# Microcontroller.net
KiCad netlist of a schematic drawn in Altium Designer
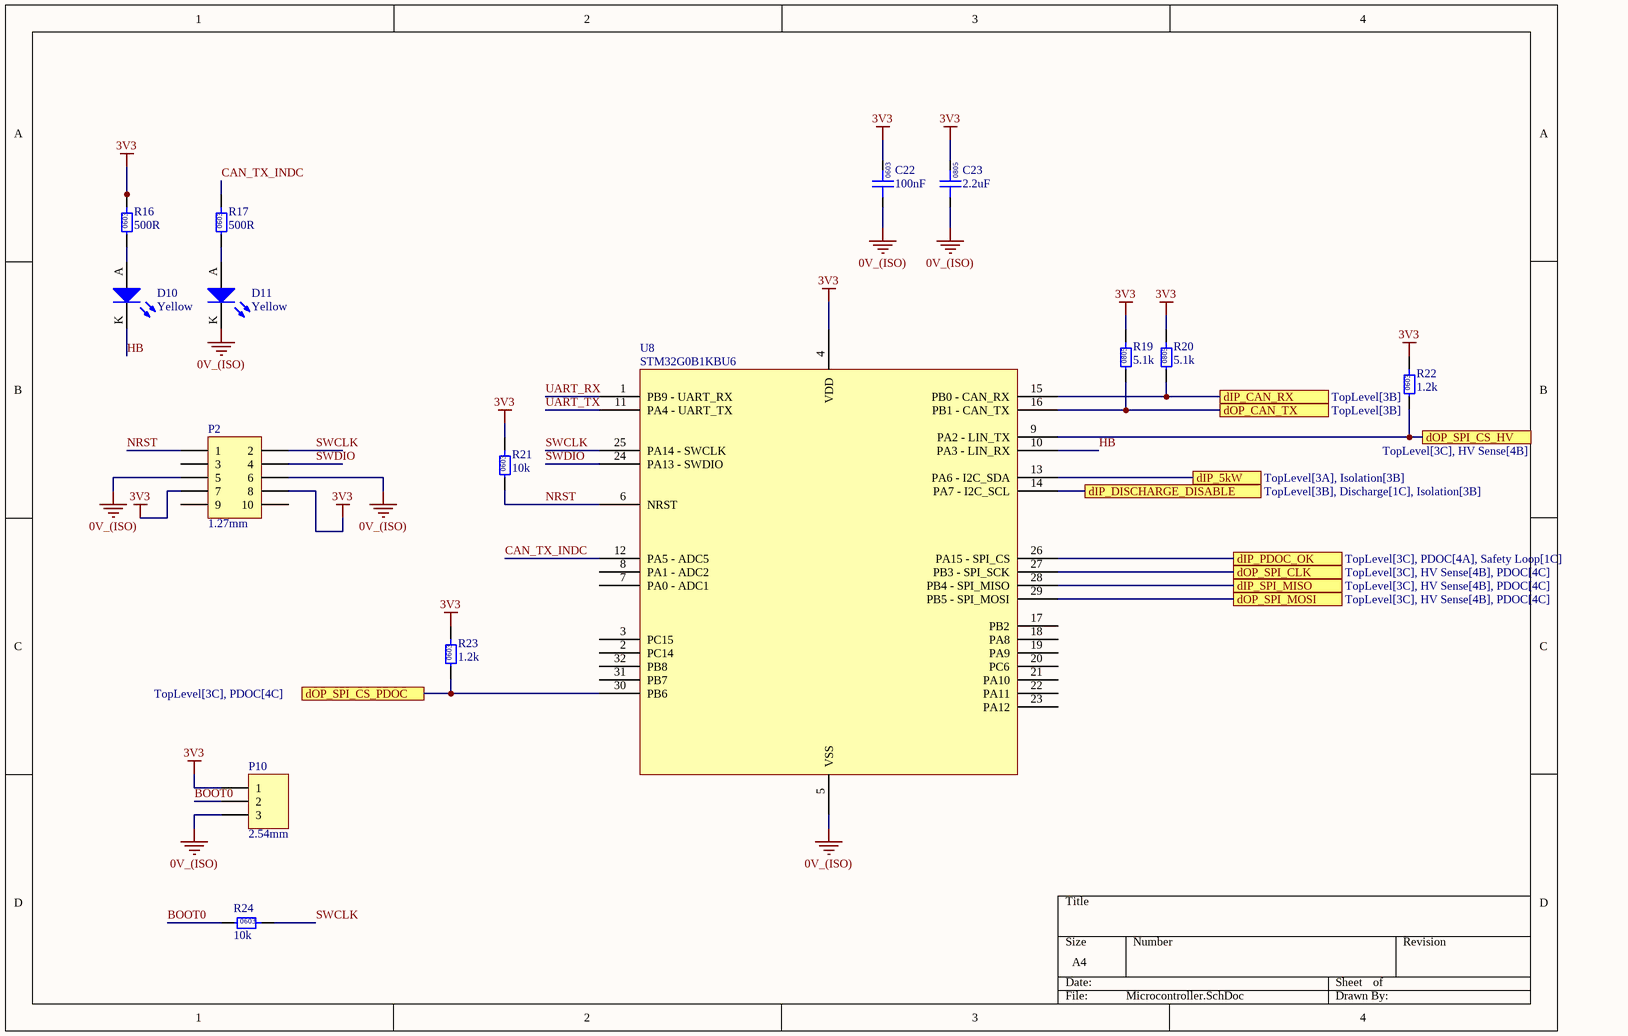
[diagram p0: Microcontroller.SchDoc]

(export (version "E")
  (design (tool "Eeschema 10.0.6"))
  (components
    (comp (ref "C22")
      (value "100nF")
      (footprint "0603 Capacitor")
      (fields (field (name "TOLERANCE") "10%") (field (name "PART NUMBER") "GCM188L81H104KA57D"))
      (libsource (lib "Team Swinburne") (part "100nF"))
    )
    (comp (ref "C23")
      (value "2.2uF")
      (footprint "GCM21BR71H105KA03L-Footprint-1")
      (fields (field (name "TOLERANCE") "10%") (field (name "PART NUMBER") "GRM21BR71E225KE11L"))
      (libsource (lib "Team Swinburne") (part "Component_1"))
    )
    (comp (ref "D10")
      (value "Yellow")
      (footprint "0805 LED")
      (description "Yellow LED Indication - Discrete 1.75V 0805 (2012 Metric)")
      (fields (field (name "PART NUMBER") "SML-211YTT86") (field (name "MANUFACTURER") "ROHM Semiconductor"))
      (libsource (lib "ts_standard_library") (part "LED"))
    )
    (comp (ref "D11")
      (value "Yellow")
      (footprint "0805 LED")
      (description "Yellow LED Indication - Discrete 1.75V 0805 (2012 Metric)")
      (fields (field (name "PART NUMBER") "SML-211YTT86") (field (name "MANUFACTURER") "ROHM Semiconductor"))
      (libsource (lib "ts_standard_library") (part "LED"))
    )
    (comp (ref "P2")
      (value "1.27mm")
      (footprint "3221-10-0300-00")
      (fields
        (field (name "PART NUMBER") "SMD 1.27mm Header 2x5 (3221-10-0300-00)")
        (field (name "CONTACT") "NA")
      )
      (libsource (lib "ts_standard_connectors") (part "Header 2x5"))
    )
    (comp (ref "P10")
      (value "2.54mm")
      (footprint "TH 2.54mm Header 1x3")
      (fields (field (name "PART NUMBER") "TH 2.54mm Header 1x3") (field (name "CONTACT") "NA"))
      (libsource (lib "ts_standard_connectors") (part "Header 1x3"))
    )
    (comp (ref "R16")
      (value "500R")
      (footprint "0603")
      (fields
        (field (name "PART NUMBER") "RT0603BRD07500RL")
        (field (name "MANUFACTURER") "YAGEO")
        (field (name "TOLERANCE") "0.01")
      )
      (libsource (lib "ts_standard_library") (part "Resistor 0603"))
    )
    (comp (ref "R17")
      (value "500R")
      (footprint "0603")
      (fields
        (field (name "PART NUMBER") "RT0603BRD07500RL")
        (field (name "MANUFACTURER") "YAGEO")
        (field (name "TOLERANCE") "0.01")
      )
      (libsource (lib "ts_standard_library") (part "Resistor 0603"))
    )
    (comp (ref "R19")
      (value "5.1k")
      (footprint "0805")
      (fields
        (field (name "PART NUMBER") "RC0805FR075K1L")
        (field (name "MANUFACTURER") "YAGEO")
        (field (name "TOLERANCE") "0.01")
      )
      (libsource (lib "ts_standard_library") (part "Resistor 0805"))
    )
    (comp (ref "R20")
      (value "5.1k")
      (footprint "0805")
      (fields
        (field (name "PART NUMBER") "RC0805FR075K1L")
        (field (name "MANUFACTURER") "YAGEO")
        (field (name "TOLERANCE") "0.01")
      )
      (libsource (lib "ts_standard_library") (part "Resistor 0805"))
    )
    (comp (ref "R21")
      (value "10k")
      (footprint "0603")
      (fields
        (field (name "PART NUMBER") "RC0603FR-0710KL")
        (field (name "MANUFACTURER") "YAGEO")
        (field (name "TOLERANCE") "0.01")
      )
      (libsource (lib "ts_standard_library") (part "Resistor 0603"))
    )
    (comp (ref "R22")
      (value "1.2k")
      (footprint "0603")
      (fields
        (field (name "PART NUMBER") "RC0603JR-071K2L")
        (field (name "MANUFACTURER") "YAGEO")
        (field (name "TOLERANCE") "0.01")
      )
      (libsource (lib "ts_standard_library") (part "Resistor 0603"))
    )
    (comp (ref "R23")
      (value "1.2k")
      (footprint "0603")
      (fields
        (field (name "PART NUMBER") "RC0603JR-071K2L")
        (field (name "MANUFACTURER") "YAGEO")
        (field (name "TOLERANCE") "0.01")
      )
      (libsource (lib "ts_standard_library") (part "Resistor 0603"))
    )
    (comp (ref "R24")
      (value "10k")
      (footprint "0603")
      (fields
        (field (name "PART NUMBER") "RC0603FR-0710KL")
        (field (name "MANUFACTURER") "YAGEO")
        (field (name "TOLERANCE") "0.01")
      )
      (libsource (lib "ts_standard_library") (part "Resistor 0603"))
    )
    (comp (ref "U8")
      (value "STM32G0B1KBU6")
      (footprint "ST-UFQFPN32")
      (description "RISC Microcontroller, 32-Bit, FLASH, Cortex-M0+ CPU, 64MHz, CMOS")
      (libsource (lib "Team Swinburne") (part "STM32G0B1KBU6"))
    )
  )
  (nets
    (net (code "1") (name "/BOOT0") (class "Default")
      (node (ref "P10") (pin "2") (pinfunction "2_2") (pintype "passive"))
      (node (ref "R24") (pin "1") (pinfunction "1_1") (pintype "passive"))
    )
    (net (code "2") (name "/CAN_TX_INDC") (class "Default")
      (node (ref "R17") (pin "2") (pinfunction "2_2") (pintype "passive"))
      (node (ref "U8") (pin "12") (pinfunction "PA5_-_ADC5_12") (pintype "passive"))
    )
    (net (code "3") (name "/HB") (class "Default")
      (node (ref "D10") (pin "K") (pinfunction "K_K") (pintype "passive"))
      (node (ref "U8") (pin "10") (pinfunction "PA3_-_LIN_RX_10") (pintype "passive"))
    )
    (net (code "4") (name "/NRST") (class "Default")
      (node (ref "P2") (pin "1") (pinfunction "1_1") (pintype "passive"))
      (node (ref "R21") (pin "1") (pinfunction "1_1") (pintype "passive"))
      (node (ref "U8") (pin "6") (pinfunction "NRST_6") (pintype "passive"))
    )
    (net (code "5") (name "/SWCLK") (class "Default")
      (node (ref "P2") (pin "2") (pinfunction "2_2") (pintype "passive"))
      (node (ref "R24") (pin "2") (pinfunction "2_2") (pintype "passive"))
      (node (ref "U8") (pin "25") (pinfunction "PA14_-_SWCLK_25") (pintype "passive"))
    )
    (net (code "6") (name "/SWDIO") (class "Default")
      (node (ref "P2") (pin "4") (pinfunction "4_4") (pintype "passive"))
      (node (ref "U8") (pin "24") (pinfunction "PA13_-_SWDIO_24") (pintype "passive"))
    )
    (net (code "7") (name "/UART_RX") (class "Default")
      (node (ref "U8") (pin "1") (pinfunction "PB9_-_UART_RX_1") (pintype "passive"))
    )
    (net (code "8") (name "/UART_TX") (class "Default")
      (node (ref "U8") (pin "11") (pinfunction "PA4_-_UART_TX_11") (pintype "passive"))
    )
    (net (code "9") (name "/dIP_5kW") (class "Default")
      (node (ref "U8") (pin "13") (pinfunction "PA6_-_I2C_SDA_13") (pintype "passive"))
    )
    (net (code "10") (name "/dIP_CAN_RX") (class "Default")
      (node (ref "R20") (pin "1") (pinfunction "1_1") (pintype "passive"))
      (node (ref "U8") (pin "15") (pinfunction "PB0_-_CAN_RX_15") (pintype "passive"))
    )
    (net (code "11") (name "/dIP_DISCHARGE_DISABLE") (class "Default")
      (node (ref "U8") (pin "14") (pinfunction "PA7_-_I2C_SCL_14") (pintype "passive"))
    )
    (net (code "12") (name "/dIP_PDOC_OK") (class "Default")
      (node (ref "U8") (pin "26") (pinfunction "PA15_-_SPI_CS_26") (pintype "passive"))
    )
    (net (code "13") (name "/dIP_SPI_MISO") (class "Default")
      (node (ref "U8") (pin "28") (pinfunction "PB4_-_SPI_MISO_28") (pintype "passive"))
    )
    (net (code "14") (name "/dOP_CAN_TX") (class "Default")
      (node (ref "R19") (pin "1") (pinfunction "1_1") (pintype "passive"))
      (node (ref "U8") (pin "16") (pinfunction "PB1_-_CAN_TX_16") (pintype "passive"))
    )
    (net (code "15") (name "/dOP_SPI_CLK") (class "Default")
      (node (ref "U8") (pin "27") (pinfunction "PB3_-_SPI_SCK_27") (pintype "passive"))
    )
    (net (code "16") (name "/dOP_SPI_CS_HV") (class "Default")
      (node (ref "R22") (pin "1") (pinfunction "1_1") (pintype "passive"))
      (node (ref "U8") (pin "9") (pinfunction "PA2_-_LIN_TX_9") (pintype "passive"))
    )
    (net (code "17") (name "/dOP_SPI_CS_PDOC") (class "Default")
      (node (ref "R23") (pin "1") (pinfunction "1_1") (pintype "passive"))
      (node (ref "U8") (pin "30") (pinfunction "PB6_30") (pintype "passive"))
    )
    (net (code "18") (name "/dOP_SPI_MOSI") (class "Default")
      (node (ref "U8") (pin "29") (pinfunction "PB5_-_SPI_MOSI_29") (pintype "passive"))
    )
    (net (code "19") (name "0V_(ISO)") (class "Default")
      (node (ref "C22") (pin "1") (pinfunction "1_1") (pintype "passive"))
      (node (ref "C23") (pin "1") (pinfunction "1_1") (pintype "passive"))
      (node (ref "D11") (pin "K") (pinfunction "K_K") (pintype "passive"))
      (node (ref "P10") (pin "3") (pinfunction "3_3") (pintype "passive"))
      (node (ref "P2") (pin "5") (pinfunction "5_5") (pintype "passive"))
      (node (ref "P2") (pin "6") (pinfunction "6_6") (pintype "passive"))
      (node (ref "U8") (pin "5") (pinfunction "VSS_5") (pintype "passive"))
    )
    (net (code "20") (name "3V3") (class "Default")
      (node (ref "C22") (pin "2") (pinfunction "2_2") (pintype "passive"))
      (node (ref "C23") (pin "2") (pinfunction "2_2") (pintype "passive"))
      (node (ref "P10") (pin "1") (pinfunction "1_1") (pintype "passive"))
      (node (ref "P2") (pin "7") (pinfunction "7_7") (pintype "passive"))
      (node (ref "P2") (pin "8") (pinfunction "8_8") (pintype "passive"))
      (node (ref "R16") (pin "2") (pinfunction "2_2") (pintype "passive"))
      (node (ref "R19") (pin "2") (pinfunction "2_2") (pintype "passive"))
      (node (ref "R20") (pin "2") (pinfunction "2_2") (pintype "passive"))
      (node (ref "R21") (pin "2") (pinfunction "2_2") (pintype "passive"))
      (node (ref "R22") (pin "2") (pinfunction "2_2") (pintype "passive"))
      (node (ref "R23") (pin "2") (pinfunction "2_2") (pintype "passive"))
      (node (ref "U8") (pin "4") (pinfunction "VDD_4") (pintype "passive"))
    )
    (net (code "21") (name "Net-(D10-PadA)") (class "Default")
      (node (ref "D10") (pin "A") (pinfunction "A_A") (pintype "passive"))
      (node (ref "R16") (pin "1") (pinfunction "1_1") (pintype "passive"))
    )
    (net (code "22") (name "Net-(D11-PadA)") (class "Default")
      (node (ref "D11") (pin "A") (pinfunction "A_A") (pintype "passive"))
      (node (ref "R17") (pin "1") (pinfunction "1_1") (pintype "passive"))
    )
    (net (code "23") (name "unconnected-(P2-Pad3)") (class "Default")
      (node (ref "P2") (pin "3") (pinfunction "3_3") (pintype "passive"))
    )
    (net (code "24") (name "unconnected-(P2-Pad9)") (class "Default")
      (node (ref "P2") (pin "9") (pinfunction "9_9") (pintype "passive"))
    )
    (net (code "25") (name "unconnected-(P2-Pad10)") (class "Default")
      (node (ref "P2") (pin "10") (pinfunction "10_10") (pintype "passive"))
    )
    (net (code "26") (name "unconnected-(U8-PA0_-_ADC1-Pad7)") (class "Default")
      (node (ref "U8") (pin "7") (pinfunction "PA0_-_ADC1_7") (pintype "passive"))
    )
    (net (code "27") (name "unconnected-(U8-PA1_-_ADC2-Pad8)") (class "Default")
      (node (ref "U8") (pin "8") (pinfunction "PA1_-_ADC2_8") (pintype "passive"))
    )
    (net (code "28") (name "unconnected-(U8-PA8-Pad18)") (class "Default")
      (node (ref "U8") (pin "18") (pinfunction "PA8_18") (pintype "passive"))
    )
    (net (code "29") (name "unconnected-(U8-PA9-Pad19)") (class "Default")
      (node (ref "U8") (pin "19") (pinfunction "PA9_19") (pintype "passive"))
    )
    (net (code "30") (name "unconnected-(U8-PA10-Pad21)") (class "Default")
      (node (ref "U8") (pin "21") (pinfunction "PA10_21") (pintype "passive"))
    )
    (net (code "31") (name "unconnected-(U8-PA11-Pad22)") (class "Default")
      (node (ref "U8") (pin "22") (pinfunction "PA11_22") (pintype "passive"))
    )
    (net (code "32") (name "unconnected-(U8-PA12-Pad23)") (class "Default")
      (node (ref "U8") (pin "23") (pinfunction "PA12_23") (pintype "passive"))
    )
    (net (code "33") (name "unconnected-(U8-PB2-Pad17)") (class "Default")
      (node (ref "U8") (pin "17") (pinfunction "PB2_17") (pintype "passive"))
    )
    (net (code "34") (name "unconnected-(U8-PB7-Pad31)") (class "Default")
      (node (ref "U8") (pin "31") (pinfunction "PB7_31") (pintype "passive"))
    )
    (net (code "35") (name "unconnected-(U8-PB8-Pad32)") (class "Default")
      (node (ref "U8") (pin "32") (pinfunction "PB8_32") (pintype "passive"))
    )
    (net (code "36") (name "unconnected-(U8-PC6-Pad20)") (class "Default")
      (node (ref "U8") (pin "20") (pinfunction "PC6_20") (pintype "passive"))
    )
    (net (code "37") (name "unconnected-(U8-PC14-Pad2)") (class "Default")
      (node (ref "U8") (pin "2") (pinfunction "PC14_2") (pintype "passive"))
    )
    (net (code "38") (name "unconnected-(U8-PC15-Pad3)") (class "Default")
      (node (ref "U8") (pin "3") (pinfunction "PC15_3") (pintype "passive"))
    )
  )
)
